# main.net
KiCad netlist of a schematic drawn in EAGLE
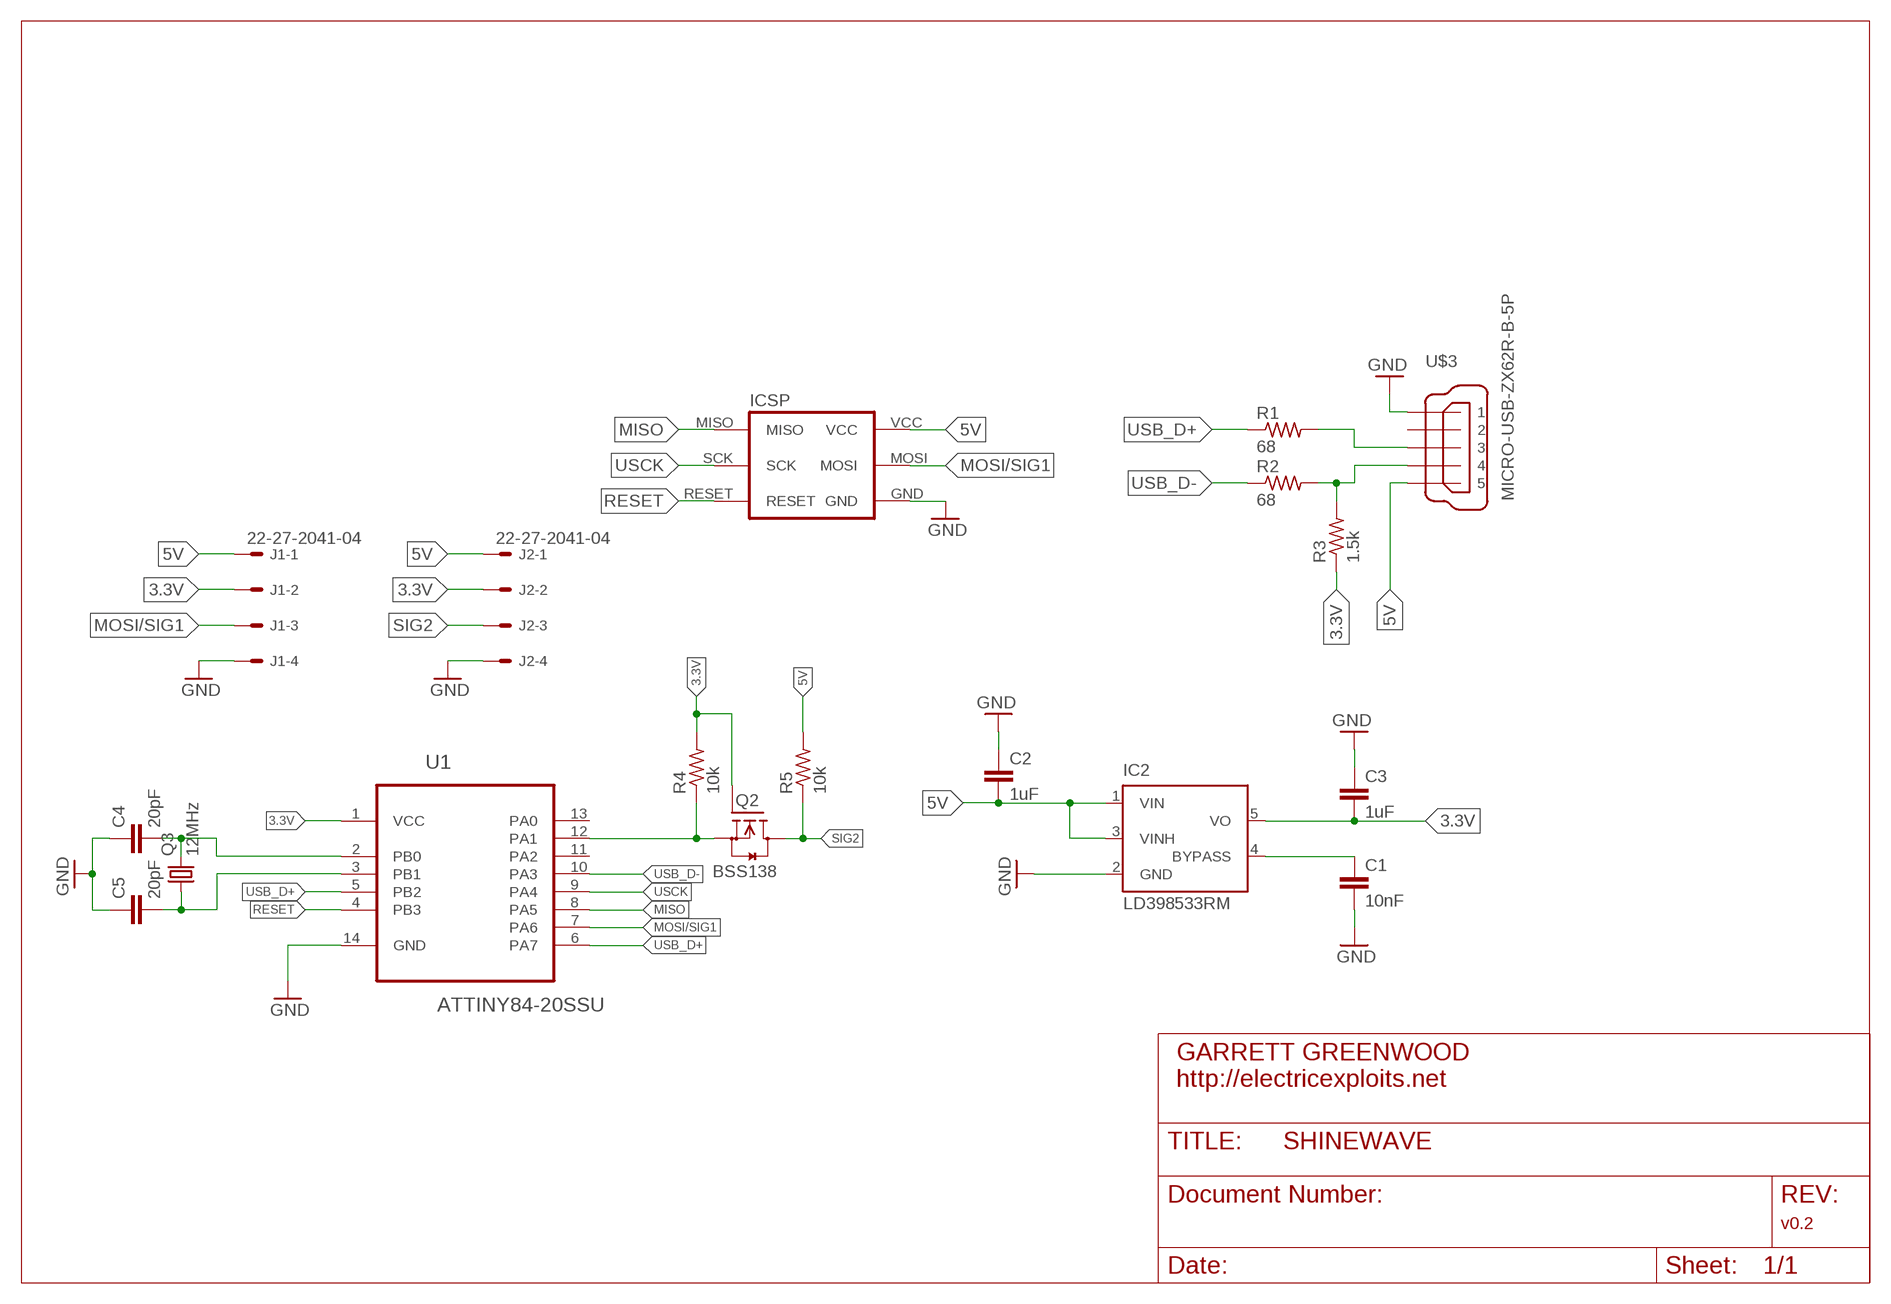
[diagram p0: schematic, sheet 1]

(export (version "E")
  (design (tool "Eeschema 10.0.6"))
  (components
    (comp (ref "C1")
      (value "10nF")
      (footprint "eagle-import:C0603")
      (libsource (lib "eagle-import") (part "C-EUC0603"))
    )
    (comp (ref "C2")
      (value "1uF")
      (footprint "eagle-import:C0603")
      (libsource (lib "eagle-import") (part "C-EUC0603"))
    )
    (comp (ref "C3")
      (value "1uF")
      (footprint "eagle-import:C0603")
      (libsource (lib "eagle-import") (part "C-EUC0603"))
    )
    (comp (ref "C4")
      (value "20pF")
      (footprint "eagle-import:C0603")
      (libsource (lib "eagle-import") (part "C-EUC0603"))
    )
    (comp (ref "C5")
      (value "20pF")
      (footprint "eagle-import:C0603")
      (libsource (lib "eagle-import") (part "C-EUC0603"))
    )
    (comp (ref "IC2")
      (value "LD398533RM")
      (footprint "eagle-import:SOT23-5L")
      (libsource (lib "eagle-import") (part "LD3985M33R"))
    )
    (comp (ref "J1")
      (value "22-27-2041-04")
      (footprint "eagle-import:6410-04")
      (libsource (lib "eagle-import") (part "22-?-0427-2041"))
    )
    (comp (ref "J2")
      (value "22-27-2041-04")
      (footprint "eagle-import:6410-04")
      (libsource (lib "eagle-import") (part "22-?-0427-2041"))
    )
    (comp (ref "Q2")
      (value "BSS138")
      (footprint "eagle-import:SOT23")
      (libsource (lib "eagle-import") (part "BSS138"))
    )
    (comp (ref "Q3")
      (value "12MHz")
      (footprint "eagle-import:CTS406")
      (libsource (lib "eagle-import") (part "CRYSTALCTS406"))
    )
    (comp (ref "R1")
      (value "68")
      (footprint "eagle-import:R0603")
      (libsource (lib "eagle-import") (part "R-US_R0603"))
    )
    (comp (ref "R2")
      (value "68")
      (footprint "eagle-import:R0603")
      (libsource (lib "eagle-import") (part "R-US_R0603"))
    )
    (comp (ref "R3")
      (value "1.5k")
      (footprint "eagle-import:R0603")
      (libsource (lib "eagle-import") (part "R-US_R0603"))
    )
    (comp (ref "R4")
      (value "10k")
      (footprint "eagle-import:R0603")
      (libsource (lib "eagle-import") (part "R-US_R0603"))
    )
    (comp (ref "R5")
      (value "10k")
      (footprint "eagle-import:R0603")
      (libsource (lib "eagle-import") (part "R-US_R0603"))
    )
    (comp (ref "U$1")
      (value "ICSP_POGO_INTERFACE")
      (footprint "eagle-import:ICSP_SMD")
      (libsource (lib "eagle-import") (part "ICSP_POGO_INTERFACE"))
    )
    (comp (ref "U$3")
      (value "MICRO-USB-ZX62R-B-5P")
      (footprint "eagle-import:ZX62R-B-5P")
      (libsource (lib "eagle-import") (part "MICRO-USB-ZX62R-B-5P"))
    )
    (comp (ref "U1")
      (value "ATTINY84-20SSU")
      (footprint "eagle-import:SOIC127P600X175-14N")
      (libsource (lib "eagle-import") (part "ATTINY84-20SSU"))
    )
  )
  (nets
    (net (code "1") (name "3.3V") (class "Default")
      (node (ref "C3") (pin "2") (pinfunction "2_2") (pintype "passive"))
      (node (ref "IC2") (pin "5") (pinfunction "VO_5") (pintype "output"))
      (node (ref "J1") (pin "2") (pinfunction "S_2") (pintype "passive"))
      (node (ref "J2") (pin "2") (pinfunction "S_2") (pintype "passive"))
      (node (ref "Q2") (pin "1") (pinfunction "G_1") (pintype "passive"))
      (node (ref "R3") (pin "1") (pinfunction "1_1") (pintype "passive"))
      (node (ref "R4") (pin "2") (pinfunction "2_2") (pintype "passive"))
      (node (ref "U1") (pin "1") (pinfunction "VCC_1") (pintype "power_in"))
    )
    (net (code "2") (name "5V") (class "Default")
      (node (ref "C2") (pin "2") (pinfunction "2_2") (pintype "passive"))
      (node (ref "IC2") (pin "1") (pinfunction "VIN_1") (pintype "input"))
      (node (ref "IC2") (pin "3") (pinfunction "VINH_3") (pintype "input"))
      (node (ref "J1") (pin "1") (pinfunction "S_1") (pintype "passive"))
      (node (ref "J2") (pin "1") (pinfunction "S_1") (pintype "passive"))
      (node (ref "R5") (pin "2") (pinfunction "2_2") (pintype "passive"))
      (node (ref "U$1") (pin "VCC") (pinfunction "VCC_VCC") (pintype "bidirectional"))
      (node (ref "U$3") (pin "5") (pinfunction "5_5") (pintype "input"))
    )
    (net (code "3") (name "GND") (class "Default")
      (node (ref "C1") (pin "2") (pinfunction "2_2") (pintype "passive"))
      (node (ref "C2") (pin "1") (pinfunction "1_1") (pintype "passive"))
      (node (ref "C3") (pin "1") (pinfunction "1_1") (pintype "passive"))
      (node (ref "C4") (pin "1") (pinfunction "1_1") (pintype "passive"))
      (node (ref "C5") (pin "1") (pinfunction "1_1") (pintype "passive"))
      (node (ref "IC2") (pin "2") (pinfunction "GND_2") (pintype "power_in"))
      (node (ref "J1") (pin "4") (pinfunction "S_4") (pintype "passive"))
      (node (ref "J2") (pin "4") (pinfunction "S_4") (pintype "passive"))
      (node (ref "U$1") (pin "GND") (pinfunction "GND_GND") (pintype "bidirectional"))
      (node (ref "U$3") (pin "1") (pinfunction "1_1") (pintype "input"))
      (node (ref "U1") (pin "14") (pinfunction "GND_14") (pintype "passive"))
    )
    (net (code "4") (name "MISO") (class "Default")
      (node (ref "U$1") (pin "MISO") (pinfunction "MISO_MISO") (pintype "bidirectional"))
      (node (ref "U1") (pin "8") (pinfunction "PA5_8") (pintype "bidirectional"))
    )
    (net (code "5") (name "MOSI{slash}SIG1") (class "Default")
      (node (ref "J1") (pin "3") (pinfunction "S_3") (pintype "passive"))
      (node (ref "U$1") (pin "MOSI") (pinfunction "MOSI_MOSI") (pintype "bidirectional"))
      (node (ref "U1") (pin "7") (pinfunction "PA6_7") (pintype "bidirectional"))
    )
    (net (code "6") (name "Net-(IC2-BYPASS)") (class "Default")
      (node (ref "C1") (pin "1") (pinfunction "1_1") (pintype "passive"))
      (node (ref "IC2") (pin "4") (pinfunction "BYPASS_4") (pintype "passive"))
    )
    (net (code "7") (name "Net-(Q2-S)") (class "Default")
      (node (ref "Q2") (pin "2") (pinfunction "S_2") (pintype "passive"))
      (node (ref "R4") (pin "1") (pinfunction "1_1") (pintype "passive"))
      (node (ref "U1") (pin "12") (pinfunction "PA1_12") (pintype "bidirectional"))
    )
    (net (code "8") (name "Net-(Q3-2)") (class "Default")
      (node (ref "C4") (pin "2") (pinfunction "2_2") (pintype "passive"))
      (node (ref "Q3") (pin "3") (pinfunction "2_3") (pintype "passive"))
      (node (ref "U1") (pin "2") (pinfunction "PB0_2") (pintype "bidirectional"))
    )
    (net (code "9") (name "Net-(R1-Pad2)") (class "Default")
      (node (ref "R1") (pin "2") (pinfunction "2_2") (pintype "passive"))
      (node (ref "U$3") (pin "3") (pinfunction "3_3") (pintype "input"))
    )
    (net (code "10") (name "Net-(R2-Pad2)") (class "Default")
      (node (ref "R2") (pin "2") (pinfunction "2_2") (pintype "passive"))
      (node (ref "R3") (pin "2") (pinfunction "2_2") (pintype "passive"))
      (node (ref "U$3") (pin "4") (pinfunction "4_4") (pintype "input"))
    )
    (net (code "11") (name "Net-(U1-PB1)") (class "Default")
      (node (ref "C5") (pin "2") (pinfunction "2_2") (pintype "passive"))
      (node (ref "Q3") (pin "1") (pinfunction "1_1") (pintype "passive"))
      (node (ref "U1") (pin "3") (pinfunction "PB1_3") (pintype "bidirectional"))
    )
    (net (code "12") (name "RESET") (class "Default")
      (node (ref "U$1") (pin "RESET") (pinfunction "RESET_RESET") (pintype "bidirectional"))
      (node (ref "U1") (pin "4") (pinfunction "PB3_4") (pintype "bidirectional"))
    )
    (net (code "13") (name "SIG2") (class "Default")
      (node (ref "J2") (pin "3") (pinfunction "S_3") (pintype "passive"))
      (node (ref "Q2") (pin "3") (pinfunction "D_3") (pintype "passive"))
      (node (ref "R5") (pin "1") (pinfunction "1_1") (pintype "passive"))
    )
    (net (code "14") (name "USB_D+") (class "Default")
      (node (ref "R1") (pin "1") (pinfunction "1_1") (pintype "passive"))
      (node (ref "U1") (pin "5") (pinfunction "PB2_5") (pintype "bidirectional"))
      (node (ref "U1") (pin "6") (pinfunction "PA7_6") (pintype "bidirectional"))
    )
    (net (code "15") (name "USB_D-") (class "Default")
      (node (ref "R2") (pin "1") (pinfunction "1_1") (pintype "passive"))
      (node (ref "U1") (pin "10") (pinfunction "PA3_10") (pintype "bidirectional"))
    )
    (net (code "16") (name "USCK") (class "Default")
      (node (ref "U$1") (pin "SCK") (pinfunction "SCK_SCK") (pintype "bidirectional"))
      (node (ref "U1") (pin "9") (pinfunction "PA4_9") (pintype "bidirectional"))
    )
    (net (code "17") (name "unconnected-(U$3-Pad2)") (class "Default")
      (node (ref "U$3") (pin "2") (pinfunction "2_2") (pintype "input"))
    )
    (net (code "18") (name "unconnected-(U1-PA0-Pad13)") (class "Default")
      (node (ref "U1") (pin "13") (pinfunction "PA0_13") (pintype "bidirectional"))
    )
    (net (code "19") (name "unconnected-(U1-PA2-Pad11)") (class "Default")
      (node (ref "U1") (pin "11") (pinfunction "PA2_11") (pintype "bidirectional"))
    )
  )
)
